# power.net
KiCad netlist of a schematic drawn in EAGLE
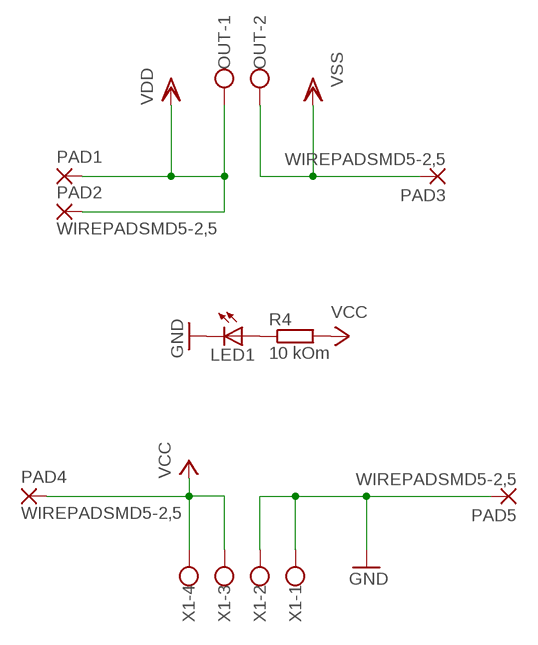
[diagram p0: schematic, sheet 1]

(export (version "E")
  (design (tool "Eeschema 10.0.6"))
  (components
    (comp (ref "LED1")
      (value "LED3MM")
      (footprint "eagle-import:LED3MM")
      (libsource (lib "eagle-import") (part "LED3MM"))
    )
    (comp (ref "OUT")
      (value "W237-102")
      (footprint "eagle-import:W237-102")
      (fields (field (name "MPN") "237-102"))
      (libsource (lib "eagle-import") (part "W237-102"))
    )
    (comp (ref "PAD1")
      (value "2,54/1,0")
      (footprint "eagle-import:2,54_1,0")
      (libsource (lib "eagle-import") (part "2,54/1,0"))
    )
    (comp (ref "PAD2")
      (value "WIREPADSMD5-2,5")
      (footprint "eagle-import:5-2,5")
      (libsource (lib "eagle-import") (part "WIREPADSMD5-2,5"))
    )
    (comp (ref "PAD3")
      (value "WIREPADSMD5-2,5")
      (footprint "eagle-import:5-2,5")
      (libsource (lib "eagle-import") (part "WIREPADSMD5-2,5"))
    )
    (comp (ref "PAD4")
      (value "WIREPADSMD5-2,5")
      (footprint "eagle-import:5-2,5")
      (libsource (lib "eagle-import") (part "WIREPADSMD5-2,5"))
    )
    (comp (ref "PAD5")
      (value "WIREPADSMD5-2,5")
      (footprint "eagle-import:5-2,5")
      (libsource (lib "eagle-import") (part "WIREPADSMD5-2,5"))
    )
    (comp (ref "R4")
      (value "10 kOm")
      (footprint "eagle-import:0207_7")
      (libsource (lib "eagle-import") (part "R-EU_0207/7"))
    )
    (comp (ref "X1")
      (value "W237-4")
      (footprint "eagle-import:W237-4")
      (libsource (lib "eagle-import") (part "W237-4"))
    )
  )
  (nets
    (net (code "1") (name "GND") (class "Default")
      (node (ref "LED1") (pin "K") (pinfunction "C_K") (pintype "passive"))
      (node (ref "PAD5") (pin "1") (pinfunction "P_1") (pintype "passive"))
      (node (ref "X1") (pin "1") (pinfunction "KL_1") (pintype "passive"))
      (node (ref "X1") (pin "2") (pinfunction "KL_2") (pintype "passive"))
    )
    (net (code "2") (name "Net-(LED1-PadA)") (class "Default")
      (node (ref "LED1") (pin "A") (pinfunction "A_A") (pintype "passive"))
      (node (ref "R4") (pin "1") (pinfunction "1_1") (pintype "passive"))
    )
    (net (code "3") (name "VCC") (class "Default")
      (node (ref "PAD4") (pin "1") (pinfunction "P_1") (pintype "passive"))
      (node (ref "R4") (pin "2") (pinfunction "2_2") (pintype "passive"))
      (node (ref "X1") (pin "3") (pinfunction "KL_3") (pintype "passive"))
      (node (ref "X1") (pin "4") (pinfunction "KL_4") (pintype "passive"))
    )
    (net (code "4") (name "VDD") (class "Default")
      (node (ref "OUT") (pin "1") (pinfunction "KL_1") (pintype "passive"))
      (node (ref "PAD1") (pin "1") (pinfunction "P_1") (pintype "passive"))
      (node (ref "PAD2") (pin "1") (pinfunction "P_1") (pintype "passive"))
    )
    (net (code "5") (name "VSS") (class "Default")
      (node (ref "OUT") (pin "2") (pinfunction "KL_2") (pintype "passive"))
      (node (ref "PAD3") (pin "1") (pinfunction "P_1") (pintype "passive"))
    )
  )
)
